# MOD-ADC-10.net
KiCad netlist of a schematic drawn in Altium Designer
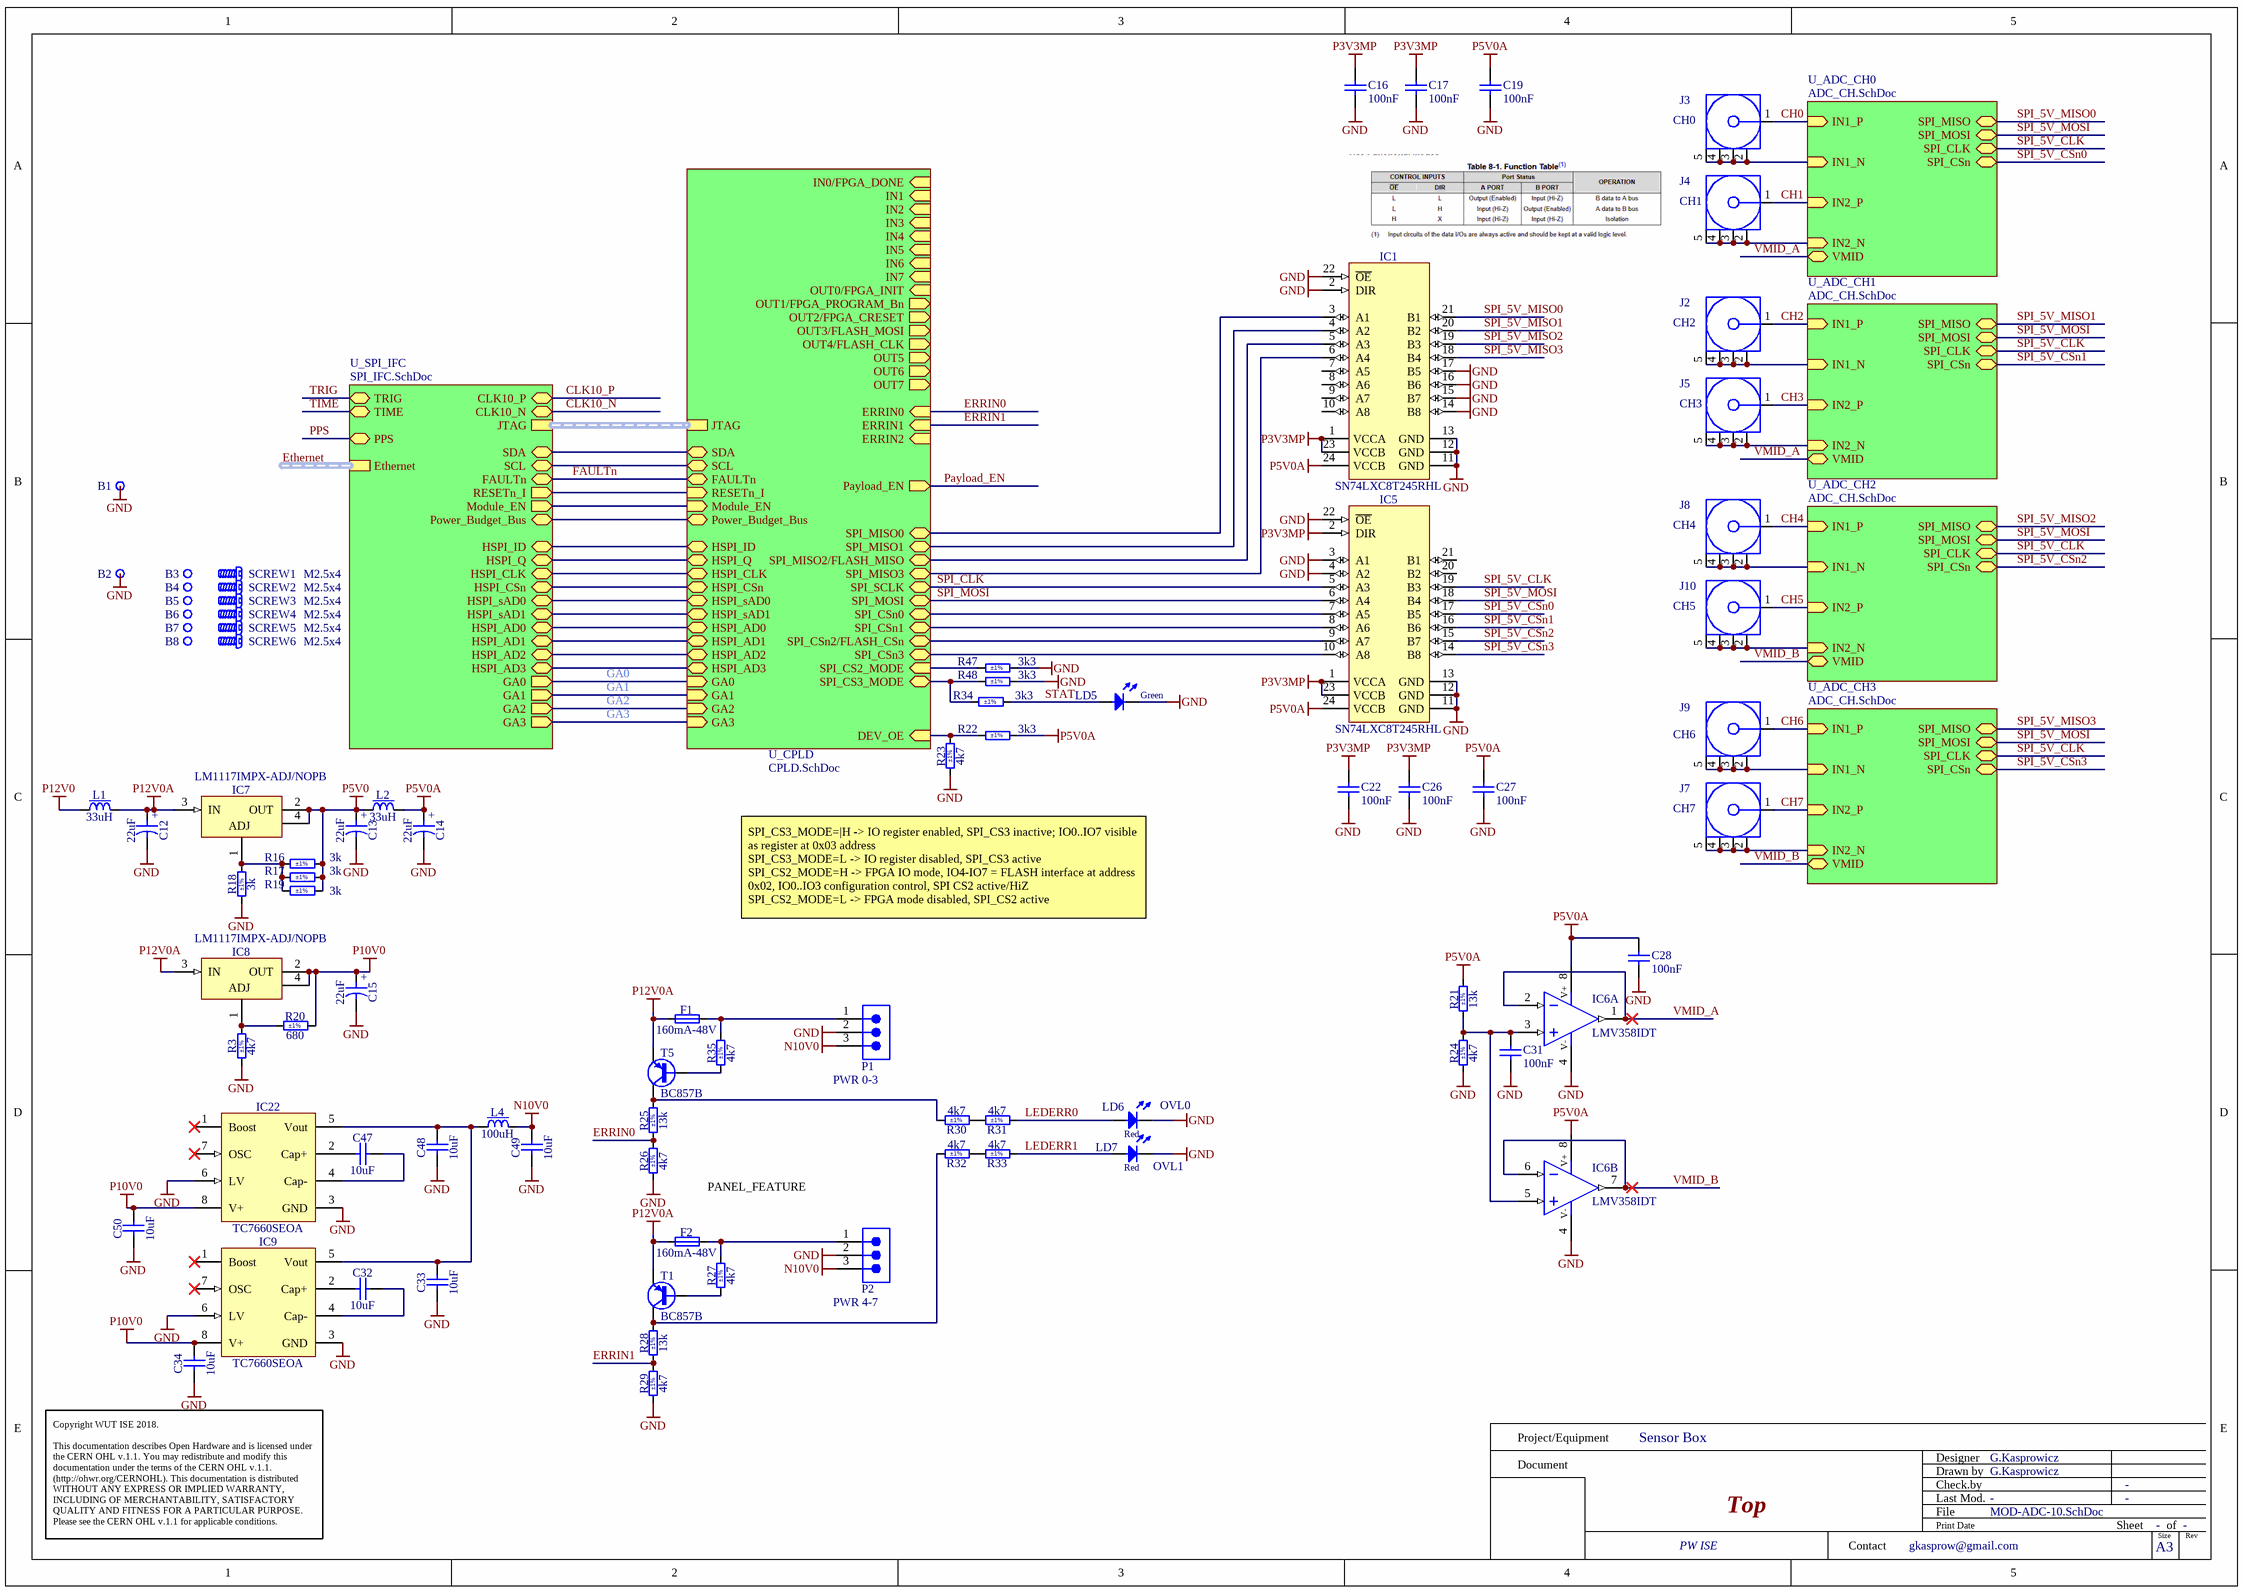
[diagram p0: MOD-ADC-10.SchDoc]

(export (version "E")
  (design (tool "Eeschema 10.0.6"))
  (components
    (comp (ref "B1")
      (value "Plated Hole")
      (footprint "MTG270_500")
      (description "Single Terminal Socket")
      (fields (field (name "PART NUMBER") "PLATED_HOLE2.7_PAD5.0") (field (name "AUTHOR") "CERN DEM JMW"))
      (libsource (lib "Eletro-mechanical") (part "Single Terminal Socket"))
    )
    (comp (ref "B2")
      (value "Plated Hole")
      (footprint "MTG270_500")
      (description "Single Terminal Socket")
      (fields (field (name "PART NUMBER") "PLATED_HOLE2.7_PAD5.0") (field (name "AUTHOR") "CERN DEM JMW"))
      (libsource (lib "Eletro-mechanical") (part "Single Terminal Socket"))
    )
    (comp (ref "B3")
      (value "Plated Hole")
      (footprint "MTG270_500")
      (description "Single Terminal Socket")
      (fields (field (name "PART NUMBER") "PLATED_HOLE2.7_PAD5.0") (field (name "AUTHOR") "CERN DEM JMW"))
      (libsource (lib "Eletro-mechanical") (part "Single Terminal Socket"))
    )
    (comp (ref "B4")
      (value "Plated Hole")
      (footprint "MTG270_500")
      (description "Single Terminal Socket")
      (fields (field (name "PART NUMBER") "PLATED_HOLE2.7_PAD5.0") (field (name "AUTHOR") "CERN DEM JMW"))
      (libsource (lib "Eletro-mechanical") (part "Single Terminal Socket"))
    )
    (comp (ref "B5")
      (value "Plated Hole")
      (footprint "MTG270_500")
      (description "Single Terminal Socket")
      (fields (field (name "PART NUMBER") "PLATED_HOLE2.7_PAD5.0") (field (name "AUTHOR") "CERN DEM JMW"))
      (libsource (lib "Eletro-mechanical") (part "Single Terminal Socket"))
    )
    (comp (ref "B6")
      (value "Plated Hole")
      (footprint "MTG270_500")
      (description "Single Terminal Socket")
      (fields (field (name "PART NUMBER") "PLATED_HOLE2.7_PAD5.0") (field (name "AUTHOR") "CERN DEM JMW"))
      (libsource (lib "Eletro-mechanical") (part "Single Terminal Socket"))
    )
    (comp (ref "B7")
      (value "Plated Hole")
      (footprint "MTG270_500")
      (description "Single Terminal Socket")
      (fields (field (name "PART NUMBER") "PLATED_HOLE2.7_PAD5.0") (field (name "AUTHOR") "CERN DEM JMW"))
      (libsource (lib "Eletro-mechanical") (part "Single Terminal Socket"))
    )
    (comp (ref "B8")
      (value "Plated Hole")
      (footprint "MTG270_500")
      (description "Single Terminal Socket")
      (fields (field (name "PART NUMBER") "PLATED_HOLE2.7_PAD5.0") (field (name "AUTHOR") "CERN DEM JMW"))
      (libsource (lib "Eletro-mechanical") (part "Single Terminal Socket"))
    )
    (comp (ref "C12")
      (value "22uF")
      (footprint "CAPMP3528X210N")
      (description "Polarised capacitor")
      (fields
        (field (name "PART NUMBER") "CTE3528-21_22UF_20V_10%")
        (field (name "VOLTAGE") "20V")
        (field (name "AUTHOR") "CERN DEM JLC")
      )
      (libsource (lib "Capacitors") (part "Capacitor - polarized"))
    )
    (comp (ref "C13")
      (value "22uF")
      (footprint "CAPMP3528X210N")
      (description "Polarised capacitor")
      (fields
        (field (name "PART NUMBER") "CTE3528-21_22UF_20V_10%")
        (field (name "VOLTAGE") "20V")
        (field (name "AUTHOR") "CERN DEM JLC")
      )
      (libsource (lib "Capacitors") (part "Capacitor - polarized"))
    )
    (comp (ref "C14")
      (value "22uF")
      (footprint "CAPMP3528X210N")
      (description "Polarised capacitor")
      (fields
        (field (name "PART NUMBER") "CTE3528-21_22UF_20V_10%")
        (field (name "VOLTAGE") "20V")
        (field (name "AUTHOR") "CERN DEM JLC")
      )
      (libsource (lib "Capacitors") (part "Capacitor - polarized"))
    )
    (comp (ref "C15")
      (value "22uF")
      (footprint "CAPMP3528X210N")
      (description "Polarised capacitor")
      (fields
        (field (name "PART NUMBER") "CTE3528-21_22UF_20V_10%")
        (field (name "VOLTAGE") "20V")
        (field (name "AUTHOR") "CERN DEM JLC")
      )
      (libsource (lib "Capacitors") (part "Capacitor - polarized"))
    )
    (comp (ref "C16")
      (value "100nF")
      (footprint "CAPC1005X55N")
      (description "Non-polarised capacitor")
      (fields
        (field (name "PART NUMBER") "CC0402_100NF_16V_10%_X7R")
        (field (name "VOLTAGE") "16V")
        (field (name "AUTHOR") "CERN DEM JLC")
      )
      (libsource (lib "Capacitors") (part "Capacitor - non polarized"))
    )
    (comp (ref "C17")
      (value "100nF")
      (footprint "CAPC1005X55N")
      (description "Non-polarised capacitor")
      (fields
        (field (name "PART NUMBER") "CC0402_100NF_16V_10%_X7R")
        (field (name "VOLTAGE") "16V")
        (field (name "AUTHOR") "CERN DEM JLC")
      )
      (libsource (lib "Capacitors") (part "Capacitor - non polarized"))
    )
    (comp (ref "C19")
      (value "100nF")
      (footprint "CAPC1005X55N")
      (description "Non-polarised capacitor")
      (fields
        (field (name "PART NUMBER") "CC0402_100NF_16V_10%_X7R")
        (field (name "VOLTAGE") "16V")
        (field (name "AUTHOR") "CERN DEM JLC")
      )
      (libsource (lib "Capacitors") (part "Capacitor - non polarized"))
    )
    (comp (ref "C22")
      (value "100nF")
      (footprint "CAPC1005X55N")
      (description "Non-polarised capacitor")
      (fields
        (field (name "PART NUMBER") "CC0402_100NF_16V_10%_X7R")
        (field (name "VOLTAGE") "16V")
        (field (name "AUTHOR") "CERN DEM JLC")
      )
      (libsource (lib "Capacitors") (part "Capacitor - non polarized"))
    )
    (comp (ref "C26")
      (value "100nF")
      (footprint "CAPC1005X55N")
      (description "Non-polarised capacitor")
      (fields
        (field (name "PART NUMBER") "CC0402_100NF_16V_10%_X7R")
        (field (name "VOLTAGE") "16V")
        (field (name "AUTHOR") "CERN DEM JLC")
      )
      (libsource (lib "Capacitors") (part "Capacitor - non polarized"))
    )
    (comp (ref "C27")
      (value "100nF")
      (footprint "CAPC1005X55N")
      (description "Non-polarised capacitor")
      (fields
        (field (name "PART NUMBER") "CC0402_100NF_16V_10%_X7R")
        (field (name "VOLTAGE") "16V")
        (field (name "AUTHOR") "CERN DEM JLC")
      )
      (libsource (lib "Capacitors") (part "Capacitor - non polarized"))
    )
    (comp (ref "C28")
      (value "100nF")
      (footprint "CAPC1005X55N")
      (description "Non-polarised capacitor")
      (fields
        (field (name "PART NUMBER") "CC0402_100NF_16V_10%_X7R")
        (field (name "VOLTAGE") "16V")
        (field (name "AUTHOR") "CERN DEM JLC")
      )
      (libsource (lib "Capacitors") (part "Capacitor - non polarized"))
    )
    (comp (ref "C31")
      (value "100nF")
      (footprint "CAPC1005X55N")
      (description "Non-polarised capacitor")
      (fields
        (field (name "PART NUMBER") "CC0402_100NF_16V_10%_X7R")
        (field (name "VOLTAGE") "16V")
        (field (name "AUTHOR") "CERN DEM JLC")
      )
      (libsource (lib "Capacitors") (part "Capacitor - non polarized"))
    )
    (comp (ref "C32")
      (value "10uF")
      (footprint "CAPC1608X80N")
      (description "Non-polarised capacitor")
      (fields
        (field (name "PART NUMBER") "CC0603_10UF_10V_10%_X5R")
        (field (name "VOLTAGE") "10V")
        (field (name "AUTHOR") "CERN DEM JLC")
      )
      (libsource (lib "Capacitors") (part "Capacitor - non polarized"))
    )
    (comp (ref "C33")
      (value "10uF")
      (footprint "CAPC1608X80N")
      (description "Non-polarised capacitor")
      (fields
        (field (name "PART NUMBER") "CC0603_10UF_10V_10%_X5R")
        (field (name "VOLTAGE") "10V")
        (field (name "AUTHOR") "CERN DEM JLC")
      )
      (libsource (lib "Capacitors") (part "Capacitor - non polarized"))
    )
    (comp (ref "C34")
      (value "10uF")
      (footprint "CAPC1608X80N")
      (description "Non-polarised capacitor")
      (fields
        (field (name "PART NUMBER") "CC0603_10UF_10V_10%_X5R")
        (field (name "VOLTAGE") "10V")
        (field (name "AUTHOR") "CERN DEM JLC")
      )
      (libsource (lib "Capacitors") (part "Capacitor - non polarized"))
    )
    (comp (ref "C47")
      (value "10uF")
      (footprint "CAPC1608X80N")
      (description "Non-polarised capacitor")
      (fields
        (field (name "PART NUMBER") "CC0603_10UF_10V_10%_X5R")
        (field (name "VOLTAGE") "10V")
        (field (name "AUTHOR") "CERN DEM JLC")
      )
      (libsource (lib "Capacitors") (part "Capacitor - non polarized"))
    )
    (comp (ref "C48")
      (value "10uF")
      (footprint "CAPC1608X80N")
      (description "Non-polarised capacitor")
      (fields
        (field (name "PART NUMBER") "CC0603_10UF_10V_10%_X5R")
        (field (name "VOLTAGE") "10V")
        (field (name "AUTHOR") "CERN DEM JLC")
      )
      (libsource (lib "Capacitors") (part "Capacitor - non polarized"))
    )
    (comp (ref "C49")
      (value "10uF")
      (footprint "CAPC1608X80N")
      (description "Non-polarised capacitor")
      (fields
        (field (name "PART NUMBER") "CC0603_10UF_10V_10%_X5R")
        (field (name "VOLTAGE") "10V")
        (field (name "AUTHOR") "CERN DEM JLC")
      )
      (libsource (lib "Capacitors") (part "Capacitor - non polarized"))
    )
    (comp (ref "C50")
      (value "10uF")
      (footprint "CAPC1608X80N")
      (description "Non-polarised capacitor")
      (fields
        (field (name "PART NUMBER") "CC0603_10UF_10V_10%_X5R")
        (field (name "VOLTAGE") "10V")
        (field (name "AUTHOR") "CERN DEM JLC")
      )
      (libsource (lib "Capacitors") (part "Capacitor - non polarized"))
    )
    (comp (ref "F1")
      (value "160mA-48V")
      (footprint "FUSRC3216X100N")
      (description "Fuse")
      (fields
        (field (name "PART NUMBER") "FUSR1206_TYCO_NANOSMD016F")
        (field (name "MANUFACTURER") "TYCO ELECTRONICS")
        (field (name "AUTHOR") "CERN DEM JLC")
      )
      (libsource (lib "Eletro-mechanical") (part "Fuse"))
    )
    (comp (ref "F2")
      (value "160mA-48V")
      (footprint "FUSRC3216X100N")
      (description "Fuse")
      (fields
        (field (name "PART NUMBER") "FUSR1206_TYCO_NANOSMD016F")
        (field (name "MANUFACTURER") "TYCO ELECTRONICS")
        (field (name "AUTHOR") "CERN DEM JLC")
      )
      (libsource (lib "Eletro-mechanical") (part "Fuse"))
    )
    (comp (ref "IC1")
      (value "SN74LXC8T245RHL")
      (footprint "TEXAS_RHL (S-PVQFN-N24)")
      (description "8-Bit Dual-Supply Bus Transceiver With Configurable Voltage Translation and 3-State Outputs")
      (fields (field (name "MANUFACTURER") "TEXAS INSTRUMENTS") (field (name "AUTHOR") "CERN DEM BC"))
      (libsource (lib "ICs And Semiconductors") (part "748T245"))
    )
    (comp (ref "IC5")
      (value "SN74LXC8T245RHL")
      (footprint "TEXAS_RHL (S-PVQFN-N24)")
      (description "8-Bit Dual-Supply Bus Transceiver With Configurable Voltage Translation and 3-State Outputs")
      (fields (field (name "MANUFACTURER") "TEXAS INSTRUMENTS") (field (name "AUTHOR") "CERN DEM BC"))
      (libsource (lib "ICs And Semiconductors") (part "748T245"))
    )
    (comp (ref "IC6")
      (value "LMV358IDT")
      (footprint "SOIC127P600X175-8N")
      (description "Dual Operational Amplifier")
      (fields (field (name "MANUFACTURER") "ST MICROELECTRONICS") (field (name "AUTHOR") "CERN DEM HF"))
      (libsource (lib "ICs And Semiconductors") (part "Operational Amplifier x2 Type1"))
    )
    (comp (ref "IC7")
      (value "LM1117IMPX-ADJ/NOPB")
      (footprint "SOT230P700X180-4N")
      (description "3-Terminal Regulator 1=Adj 2=OUT 3=IN 4=OUT")
      (fields
        (field (name "MANUFACTURER") "TEXAS INSTRUMENTS")
        (field (name "MANUFACTURER PART NUMBER") "LM1117IMPX-ADJ")
        (field (name "AUTHOR") "CERN DEM JLC")
      )
      (libsource (lib "ICs And Semiconductors") (part "REG3+1 1ADJ-2OUT-3IN+4OUT"))
    )
    (comp (ref "IC8")
      (value "LM1117IMPX-ADJ/NOPB")
      (footprint "SOT230P700X180-4N")
      (description "3-Terminal Regulator 1=Adj 2=OUT 3=IN 4=OUT")
      (fields
        (field (name "MANUFACTURER") "TEXAS INSTRUMENTS")
        (field (name "MANUFACTURER PART NUMBER") "LM1117IMPX-ADJ")
        (field (name "AUTHOR") "CERN DEM JLC")
      )
      (libsource (lib "ICs And Semiconductors") (part "REG3+1 1ADJ-2OUT-3IN+4OUT"))
    )
    (comp (ref "IC9")
      (value "TC7660SEOA")
      (footprint "SOIC127P600X175-8N")
      (description "Super Charge Pump DC-to-DC Voltage Converter")
      (fields (field (name "MANUFACTURER") "MICROCHIP TECHNOLOGY") (field (name "AUTHOR") "CERN DEM HF"))
      (libsource (lib "ICs And Semiconductors") (part "TC7660S"))
    )
    (comp (ref "IC22")
      (value "TC7660SEOA")
      (footprint "SOIC127P600X175-8N")
      (description "Super Charge Pump DC-to-DC Voltage Converter")
      (fields (field (name "MANUFACTURER") "MICROCHIP TECHNOLOGY") (field (name "AUTHOR") "CERN DEM HF"))
      (libsource (lib "ICs And Semiconductors") (part "TC7660S"))
    )
    (comp (ref "J2")
      (value "60611002111502")
      (footprint "60611002111502")
      (description "WR-MCX PCB Jack, THT, Right Angle, Solder Leg 1.73mm")
      (fields (field (name "MANUFACTURER") "Wurth Elektronik") (field (name "PANEL_LABEL") "CH2"))
      (libsource (lib "Altium_WR-MCX (rev22a)") (part "60611002111502"))
    )
    (comp (ref "J3")
      (value "60611002111502")
      (footprint "60611002111502")
      (description "WR-MCX PCB Jack, THT, Right Angle, Solder Leg 1.73mm")
      (fields (field (name "MANUFACTURER") "Wurth Elektronik") (field (name "PANEL_LABEL") "CH0"))
      (libsource (lib "Altium_WR-MCX (rev22a)") (part "60611002111502"))
    )
    (comp (ref "J4")
      (value "60611002111502")
      (footprint "60611002111502")
      (description "WR-MCX PCB Jack, THT, Right Angle, Solder Leg 1.73mm")
      (fields (field (name "MANUFACTURER") "Wurth Elektronik") (field (name "PANEL_LABEL") "CH1"))
      (libsource (lib "Altium_WR-MCX (rev22a)") (part "60611002111502"))
    )
    (comp (ref "J5")
      (value "60611002111502")
      (footprint "60611002111502")
      (description "WR-MCX PCB Jack, THT, Right Angle, Solder Leg 1.73mm")
      (fields (field (name "MANUFACTURER") "Wurth Elektronik") (field (name "PANEL_LABEL") "CH3"))
      (libsource (lib "Altium_WR-MCX (rev22a)") (part "60611002111502"))
    )
    (comp (ref "J7")
      (value "60611002111502")
      (footprint "60611002111502")
      (description "WR-MCX PCB Jack, THT, Right Angle, Solder Leg 1.73mm")
      (fields (field (name "MANUFACTURER") "Wurth Elektronik") (field (name "PANEL_LABEL") "CH7"))
      (libsource (lib "Altium_WR-MCX (rev22a)") (part "60611002111502"))
    )
    (comp (ref "J8")
      (value "60611002111502")
      (footprint "60611002111502")
      (description "WR-MCX PCB Jack, THT, Right Angle, Solder Leg 1.73mm")
      (fields (field (name "MANUFACTURER") "Wurth Elektronik") (field (name "PANEL_LABEL") "CH4"))
      (libsource (lib "Altium_WR-MCX (rev22a)") (part "60611002111502"))
    )
    (comp (ref "J9")
      (value "60611002111502")
      (footprint "60611002111502")
      (description "WR-MCX PCB Jack, THT, Right Angle, Solder Leg 1.73mm")
      (fields (field (name "MANUFACTURER") "Wurth Elektronik") (field (name "PANEL_LABEL") "CH6"))
      (libsource (lib "Altium_WR-MCX (rev22a)") (part "60611002111502"))
    )
    (comp (ref "J10")
      (value "60611002111502")
      (footprint "60611002111502")
      (description "WR-MCX PCB Jack, THT, Right Angle, Solder Leg 1.73mm")
      (fields (field (name "MANUFACTURER") "Wurth Elektronik") (field (name "PANEL_LABEL") "CH5"))
      (libsource (lib "Altium_WR-MCX (rev22a)") (part "60611002111502"))
    )
    (comp (ref "L1")
      (value "33uH")
      (footprint "IND_WURTH_WE-TPC_4828")
      (description "Inductor With Core")
      (fields
        (field (name "PART NUMBER") "IND_33UH_30%_WURTH_WE-TPC_744043330")
        (field (name "POWER") "820mA")
        (field (name "AUTHOR") "CERN DEM JLC")
      )
      (libsource (lib "Inductors & Transformers") (part "Inductor With Magnetic core"))
    )
    (comp (ref "L2")
      (value "33uH")
      (footprint "IND_WURTH_WE-TPC_4828")
      (description "Inductor With Core")
      (fields
        (field (name "PART NUMBER") "IND_33UH_30%_WURTH_WE-TPC_744043330")
        (field (name "POWER") "820mA")
        (field (name "AUTHOR") "CERN DEM JLC")
      )
      (libsource (lib "Inductors & Transformers") (part "Inductor With Magnetic core"))
    )
    (comp (ref "L4")
      (value "100uH")
      (footprint "INDM3225X240N")
      (description "Inductor With Core")
      (fields
        (field (name "PART NUMBER") "IND1210_100UH_10%_EPCOS_B82422H")
        (field (name "POWER") "150mA")
        (field (name "AUTHOR") "CERN DEM JLC")
      )
      (libsource (lib "Inductors & Transformers") (part "Inductor With Magnetic core"))
    )
    (comp (ref "LD5")
      (value "Green")
      (footprint "LED_AVAGO_HSME-C120")
      (description "LED Green 1C 2A")
      (fields
        (field (name "PART NUMBER") "LED_AVAGO_HSME-C120")
        (field (name "MANUFACTURER") "AVAGO TECHNOLOGIES")
        (field (name "AUTHOR") "CERN DEM JMW")
      )
      (libsource (lib "ICs And Semiconductors") (part "LED Green 1C 2A"))
    )
    (comp (ref "LD6")
      (value "Red")
      (footprint "LED_AVAGO_HSMC-C120")
      (description "LED Red 1C 2A")
      (fields
        (field (name "PART NUMBER") "LED_AVAGO_HSMC-C120")
        (field (name "MANUFACTURER") "AVAGO TECHNOLOGIES")
        (field (name "PANEL_LABEL") "OVL0")
        (field (name "AUTHOR") "CERN DEM JMW")
      )
      (libsource (lib "ICs And Semiconductors") (part "LED Red 1C 2A"))
    )
    (comp (ref "LD7")
      (value "Red")
      (footprint "LED_AVAGO_HSMC-C120")
      (description "LED Red 1C 2A")
      (fields
        (field (name "PART NUMBER") "LED_AVAGO_HSMC-C120")
        (field (name "MANUFACTURER") "AVAGO TECHNOLOGIES")
        (field (name "PANEL_LABEL") "OVL1")
        (field (name "AUTHOR") "CERN DEM JMW")
      )
      (libsource (lib "ICs And Semiconductors") (part "LED Red 1C 2A"))
    )
    (comp (ref "P1")
      (value "691382010003")
      (footprint "691382010003")
      (description "WR-TBL Series 382 Horizontal PCB Header, THT, pitch 2.5mm, 3p")
      (fields (field (name "MANUFACTURER") "Wurth Elektronik") (field (name "PANEL_LABEL") "PWR 0-3"))
      (libsource (lib "Altium_WR-TBL (rev23f)") (part "691382010003"))
    )
    (comp (ref "P2")
      (value "691382010003")
      (footprint "691382010003")
      (description "WR-TBL Series 382 Horizontal PCB Header, THT, pitch 2.5mm, 3p")
      (fields (field (name "MANUFACTURER") "Wurth Elektronik") (field (name "PANEL_LABEL") "PWR 4-7"))
      (libsource (lib "Altium_WR-TBL (rev23f)") (part "691382010003"))
    )
    (comp (ref "R3")
      (value "4k7")
      (footprint "RESC1608X55N")
      (description "Resistor - 1%")
      (fields
        (field (name "TOLERANCE") "±1%")
        (field (name "PART NUMBER") "R0603_4K7_1%_0.1W_100PPM")
        (field (name "POWER") "0.1W")
        (field (name "AUTHOR") "CERN DEM JLC")
      )
      (libsource (lib "Resistors") (part "Resistor - 1%"))
    )
    (comp (ref "R16")
      (value "3k")
      (footprint "RESC1608X55N")
      (description "Resistor - 1%")
      (fields
        (field (name "TOLERANCE") "±1%")
        (field (name "PART NUMBER") "R0603_3K_1%_0.33W_100PPM_VISHAY_CRCW-HP e3")
        (field (name "POWER") "0.33W")
        (field (name "AUTHOR") "CERN DEM BC")
      )
      (libsource (lib "Resistors") (part "Resistor - 1%"))
    )
    (comp (ref "R17")
      (value "3k")
      (footprint "RESC1608X55N")
      (description "Resistor - 1%")
      (fields
        (field (name "TOLERANCE") "±1%")
        (field (name "PART NUMBER") "R0603_3K_1%_0.33W_100PPM_VISHAY_CRCW-HP e3")
        (field (name "POWER") "0.33W")
        (field (name "AUTHOR") "CERN DEM BC")
      )
      (libsource (lib "Resistors") (part "Resistor - 1%"))
    )
    (comp (ref "R18")
      (value "3k")
      (footprint "RESC1608X55N")
      (description "Resistor - 1%")
      (fields
        (field (name "TOLERANCE") "±1%")
        (field (name "PART NUMBER") "R0603_3K_1%_0.33W_100PPM_VISHAY_CRCW-HP e3")
        (field (name "POWER") "0.33W")
        (field (name "AUTHOR") "CERN DEM BC")
      )
      (libsource (lib "Resistors") (part "Resistor - 1%"))
    )
    (comp (ref "R19")
      (value "3k")
      (footprint "RESC1608X55N")
      (description "Resistor - 1%")
      (fields
        (field (name "TOLERANCE") "±1%")
        (field (name "PART NUMBER") "R0603_3K_1%_0.33W_100PPM_VISHAY_CRCW-HP e3")
        (field (name "POWER") "0.33W")
        (field (name "AUTHOR") "CERN DEM BC")
      )
      (libsource (lib "Resistors") (part "Resistor - 1%"))
    )
    (comp (ref "R20")
      (value "680")
      (footprint "RESC1608X55N")
      (description "Resistor - 1%")
      (fields
        (field (name "TOLERANCE") "±1%")
        (field (name "PART NUMBER") "R0603_680R_1%_0.1W_100PPM")
        (field (name "POWER") "0.1W")
        (field (name "AUTHOR") "CERN DEM JLC")
      )
      (libsource (lib "Resistors") (part "Resistor - 1%"))
    )
    (comp (ref "R21")
      (value "13k")
      (footprint "RESC1005X40N")
      (description "Resistor - 1%")
      (fields
        (field (name "TOLERANCE") "±1%")
        (field (name "PART NUMBER") "R0402_13K_1%_0.0625W_100PPM")
        (field (name "POWER") "0.0625W")
        (field (name "AUTHOR") "CERN DEM JLC")
      )
      (libsource (lib "Resistors") (part "Resistor - 1%"))
    )
    (comp (ref "R22")
      (value "3k3")
      (footprint "RESC1005X40N")
      (description "Resistor - 1%")
      (fields
        (field (name "TOLERANCE") "±1%")
        (field (name "PART NUMBER") "R0402_3K3_1%_0.0625W_100PPM")
        (field (name "POWER") "0.0625W")
        (field (name "AUTHOR") "CERN DEM JLC")
      )
      (libsource (lib "Resistors") (part "Resistor - 1%"))
    )
    (comp (ref "R23")
      (value "4k7")
      (footprint "RESC1608X55N")
      (description "Resistor - 1%")
      (fields
        (field (name "TOLERANCE") "±1%")
        (field (name "PART NUMBER") "R0603_4K7_1%_0.1W_100PPM")
        (field (name "POWER") "0.1W")
        (field (name "AUTHOR") "CERN DEM JLC")
      )
      (libsource (lib "Resistors") (part "Resistor - 1%"))
    )
    (comp (ref "R24")
      (value "4k7")
      (footprint "RESC1608X55N")
      (description "Resistor - 1%")
      (fields
        (field (name "TOLERANCE") "±1%")
        (field (name "PART NUMBER") "R0603_4K7_1%_0.1W_100PPM")
        (field (name "POWER") "0.1W")
        (field (name "AUTHOR") "CERN DEM JLC")
      )
      (libsource (lib "Resistors") (part "Resistor - 1%"))
    )
    (comp (ref "R25")
      (value "13k")
      (footprint "RESC1005X40N")
      (description "Resistor - 1%")
      (fields
        (field (name "TOLERANCE") "±1%")
        (field (name "PART NUMBER") "R0402_13K_1%_0.0625W_100PPM")
        (field (name "POWER") "0.0625W")
        (field (name "AUTHOR") "CERN DEM JLC")
      )
      (libsource (lib "Resistors") (part "Resistor - 1%"))
    )
    (comp (ref "R26")
      (value "4k7")
      (footprint "RESC1608X55N")
      (description "Resistor - 1%")
      (fields
        (field (name "TOLERANCE") "±1%")
        (field (name "PART NUMBER") "R0603_4K7_1%_0.1W_100PPM")
        (field (name "POWER") "0.1W")
        (field (name "AUTHOR") "CERN DEM JLC")
      )
      (libsource (lib "Resistors") (part "Resistor - 1%"))
    )
    (comp (ref "R27")
      (value "4k7")
      (footprint "RESC1608X55N")
      (description "Resistor - 1%")
      (fields
        (field (name "TOLERANCE") "±1%")
        (field (name "PART NUMBER") "R0603_4K7_1%_0.1W_100PPM")
        (field (name "POWER") "0.1W")
        (field (name "AUTHOR") "CERN DEM JLC")
      )
      (libsource (lib "Resistors") (part "Resistor - 1%"))
    )
    (comp (ref "R28")
      (value "13k")
      (footprint "RESC1005X40N")
      (description "Resistor - 1%")
      (fields
        (field (name "TOLERANCE") "±1%")
        (field (name "PART NUMBER") "R0402_13K_1%_0.0625W_100PPM")
        (field (name "POWER") "0.0625W")
        (field (name "AUTHOR") "CERN DEM JLC")
      )
      (libsource (lib "Resistors") (part "Resistor - 1%"))
    )
    (comp (ref "R29")
      (value "4k7")
      (footprint "RESC1608X55N")
      (description "Resistor - 1%")
      (fields
        (field (name "TOLERANCE") "±1%")
        (field (name "PART NUMBER") "R0603_4K7_1%_0.1W_100PPM")
        (field (name "POWER") "0.1W")
        (field (name "AUTHOR") "CERN DEM JLC")
      )
      (libsource (lib "Resistors") (part "Resistor - 1%"))
    )
    (comp (ref "R30")
      (value "4k7")
      (footprint "RESC1608X55N")
      (description "Resistor - 1%")
      (fields
        (field (name "TOLERANCE") "±1%")
        (field (name "PART NUMBER") "R0603_4K7_1%_0.1W_100PPM")
        (field (name "POWER") "0.1W")
        (field (name "AUTHOR") "CERN DEM JLC")
      )
      (libsource (lib "Resistors") (part "Resistor - 1%"))
    )
    (comp (ref "R31")
      (value "4k7")
      (footprint "RESC1608X55N")
      (description "Resistor - 1%")
      (fields
        (field (name "TOLERANCE") "±1%")
        (field (name "PART NUMBER") "R0603_4K7_1%_0.1W_100PPM")
        (field (name "POWER") "0.1W")
        (field (name "AUTHOR") "CERN DEM JLC")
      )
      (libsource (lib "Resistors") (part "Resistor - 1%"))
    )
    (comp (ref "R32")
      (value "4k7")
      (footprint "RESC1608X55N")
      (description "Resistor - 1%")
      (fields
        (field (name "TOLERANCE") "±1%")
        (field (name "PART NUMBER") "R0603_4K7_1%_0.1W_100PPM")
        (field (name "POWER") "0.1W")
        (field (name "AUTHOR") "CERN DEM JLC")
      )
      (libsource (lib "Resistors") (part "Resistor - 1%"))
    )
    (comp (ref "R33")
      (value "4k7")
      (footprint "RESC1608X55N")
      (description "Resistor - 1%")
      (fields
        (field (name "TOLERANCE") "±1%")
        (field (name "PART NUMBER") "R0603_4K7_1%_0.1W_100PPM")
        (field (name "POWER") "0.1W")
        (field (name "AUTHOR") "CERN DEM JLC")
      )
      (libsource (lib "Resistors") (part "Resistor - 1%"))
    )
    (comp (ref "R34")
      (value "3k3")
      (footprint "RESC1005X40N")
      (description "Resistor - 1%")
      (fields
        (field (name "TOLERANCE") "±1%")
        (field (name "PART NUMBER") "R0402_3K3_1%_0.0625W_100PPM")
        (field (name "POWER") "0.0625W")
        (field (name "AUTHOR") "CERN DEM JLC")
      )
      (libsource (lib "Resistors") (part "Resistor - 1%"))
    )
    (comp (ref "R35")
      (value "4k7")
      (footprint "RESC1608X55N")
      (description "Resistor - 1%")
      (fields
        (field (name "TOLERANCE") "±1%")
        (field (name "PART NUMBER") "R0603_4K7_1%_0.1W_100PPM")
        (field (name "POWER") "0.1W")
        (field (name "AUTHOR") "CERN DEM JLC")
      )
      (libsource (lib "Resistors") (part "Resistor - 1%"))
    )
    (comp (ref "R47")
      (value "3k3")
      (footprint "RESC1005X40N")
      (description "Resistor - 1%")
      (fields
        (field (name "TOLERANCE") "±1%")
        (field (name "PART NUMBER") "R0402_3K3_1%_0.0625W_100PPM")
        (field (name "POWER") "0.0625W")
        (field (name "AUTHOR") "CERN DEM JLC")
      )
      (libsource (lib "Resistors") (part "Resistor - 1%"))
    )
    (comp (ref "R48")
      (value "3k3")
      (footprint "RESC1005X40N")
      (description "Resistor - 1%")
      (fields
        (field (name "TOLERANCE") "±1%")
        (field (name "PART NUMBER") "R0402_3K3_1%_0.0625W_100PPM")
        (field (name "POWER") "0.0625W")
        (field (name "AUTHOR") "CERN DEM JLC")
      )
      (libsource (lib "Resistors") (part "Resistor - 1%"))
    )
    (comp (ref "SCREW1")
      (value "M2.5x4")
      (footprint "BOSSARD_BN5687-3061587_v")
      (description "Screw")
      (fields
        (field (name "PART NUMBER") "BOSSARD_BN5687-3061587_v")
        (field (name "MANUFACTURER") "BOSSARD")
        (field (name "AUTHOR") "CERN DEM JLC")
      )
      (libsource (lib "Eletro-mechanical") (part "Screw"))
    )
    (comp (ref "SCREW2")
      (value "M2.5x4")
      (footprint "BOSSARD_BN5687-3061587_v")
      (description "Screw")
      (fields
        (field (name "PART NUMBER") "BOSSARD_BN5687-3061587_v")
        (field (name "MANUFACTURER") "BOSSARD")
        (field (name "AUTHOR") "CERN DEM JLC")
      )
      (libsource (lib "Eletro-mechanical") (part "Screw"))
    )
    (comp (ref "SCREW3")
      (value "M2.5x4")
      (footprint "BOSSARD_BN5687-3061587_v")
      (description "Screw")
      (fields
        (field (name "PART NUMBER") "BOSSARD_BN5687-3061587_v")
        (field (name "MANUFACTURER") "BOSSARD")
        (field (name "AUTHOR") "CERN DEM JLC")
      )
      (libsource (lib "Eletro-mechanical") (part "Screw"))
    )
    (comp (ref "SCREW4")
      (value "M2.5x4")
      (footprint "BOSSARD_BN5687-3061587_v")
      (description "Screw")
      (fields
        (field (name "PART NUMBER") "BOSSARD_BN5687-3061587_v")
        (field (name "MANUFACTURER") "BOSSARD")
        (field (name "AUTHOR") "CERN DEM JLC")
      )
      (libsource (lib "Eletro-mechanical") (part "Screw"))
    )
    (comp (ref "SCREW5")
      (value "M2.5x4")
      (footprint "BOSSARD_BN5687-3061587_v")
      (description "Screw")
      (fields
        (field (name "PART NUMBER") "BOSSARD_BN5687-3061587_v")
        (field (name "MANUFACTURER") "BOSSARD")
        (field (name "AUTHOR") "CERN DEM JLC")
      )
      (libsource (lib "Eletro-mechanical") (part "Screw"))
    )
    (comp (ref "SCREW6")
      (value "M2.5x4")
      (footprint "BOSSARD_BN5687-3061587_v")
      (description "Screw")
      (fields
        (field (name "PART NUMBER") "BOSSARD_BN5687-3061587_v")
        (field (name "MANUFACTURER") "BOSSARD")
        (field (name "AUTHOR") "CERN DEM JLC")
      )
      (libsource (lib "Eletro-mechanical") (part "Screw"))
    )
    (comp (ref "T1")
      (value "BC857B")
      (footprint "SOT95P230X110-3N")
      (description "PNP Transistor")
      (fields (field (name "MANUFACTURER") "NXP SEMICONDUCTORS") (field (name "AUTHOR") "CERN DEM JLC"))
      (libsource (lib "ICs And Semiconductors") (part "PNP B1 E2 C3"))
    )
    (comp (ref "T5")
      (value "BC857B")
      (footprint "SOT95P230X110-3N")
      (description "PNP Transistor")
      (fields (field (name "MANUFACTURER") "NXP SEMICONDUCTORS") (field (name "AUTHOR") "CERN DEM JLC"))
      (libsource (lib "ICs And Semiconductors") (part "PNP B1 E2 C3"))
    )
  )
  (nets
    (net (code "2") (name "/CH0") (class "Default")
      (node (ref "J3") (pin "1") (pinfunction "Signal_1") (pintype "passive"))
    )
    (net (code "3") (name "/CH1") (class "Default")
      (node (ref "J4") (pin "1") (pinfunction "Signal_1") (pintype "passive"))
    )
    (net (code "4") (name "/CH2") (class "Default")
      (node (ref "J2") (pin "1") (pinfunction "Signal_1") (pintype "passive"))
    )
    (net (code "5") (name "/CH3") (class "Default")
      (node (ref "J5") (pin "1") (pinfunction "Signal_1") (pintype "passive"))
    )
    (net (code "6") (name "/CH4") (class "Default")
      (node (ref "J8") (pin "1") (pinfunction "Signal_1") (pintype "passive"))
    )
    (net (code "7") (name "/CH5") (class "Default")
      (node (ref "J10") (pin "1") (pinfunction "Signal_1") (pintype "passive"))
    )
    (net (code "8") (name "/CH6") (class "Default")
      (node (ref "J9") (pin "1") (pinfunction "Signal_1") (pintype "passive"))
    )
    (net (code "9") (name "/CH7") (class "Default")
      (node (ref "J7") (pin "1") (pinfunction "Signal_1") (pintype "passive"))
    )
    (net (code "12") (name "/DEV_OE") (class "Default")
      (node (ref "R22") (pin "1") (pinfunction "1_1") (pintype "passive"))
      (node (ref "R23") (pin "2") (pinfunction "2_2") (pintype "passive"))
    )
    (net (code "13") (name "/ERRIN0") (class "Default")
      (node (ref "R25") (pin "1") (pinfunction "1_1") (pintype "passive"))
      (node (ref "R26") (pin "2") (pinfunction "2_2") (pintype "passive"))
    )
    (net (code "14") (name "/ERRIN1") (class "Default")
      (node (ref "R28") (pin "1") (pinfunction "1_1") (pintype "passive"))
      (node (ref "R29") (pin "2") (pinfunction "2_2") (pintype "passive"))
    )
    (net (code "33") (name "/IN1_N") (class "Default")
      (node (ref "J2") (pin "2") (pinfunction "GND_2") (pintype "passive"))
      (node (ref "J2") (pin "3") (pinfunction "GND_3") (pintype "passive"))
      (node (ref "J2") (pin "4") (pinfunction "GND_4") (pintype "passive"))
      (node (ref "J2") (pin "5") (pinfunction "GND_5") (pintype "passive"))
    )
    (net (code "34") (name "/IN1_N_1") (class "Default")
      (node (ref "J9") (pin "2") (pinfunction "GND_2") (pintype "passive"))
      (node (ref "J9") (pin "3") (pinfunction "GND_3") (pintype "passive"))
      (node (ref "J9") (pin "4") (pinfunction "GND_4") (pintype "passive"))
      (node (ref "J9") (pin "5") (pinfunction "GND_5") (pintype "passive"))
    )
    (net (code "35") (name "/IN1_N_2") (class "Default")
      (node (ref "J8") (pin "2") (pinfunction "GND_2") (pintype "passive"))
      (node (ref "J8") (pin "3") (pinfunction "GND_3") (pintype "passive"))
      (node (ref "J8") (pin "4") (pinfunction "GND_4") (pintype "passive"))
      (node (ref "J8") (pin "5") (pinfunction "GND_5") (pintype "passive"))
    )
    (net (code "36") (name "/IN1_N_3") (class "Default")
      (node (ref "J3") (pin "2") (pinfunction "GND_2") (pintype "passive"))
      (node (ref "J3") (pin "3") (pinfunction "GND_3") (pintype "passive"))
      (node (ref "J3") (pin "4") (pinfunction "GND_4") (pintype "passive"))
      (node (ref "J3") (pin "5") (pinfunction "GND_5") (pintype "passive"))
    )
    (net (code "38") (name "/IN2_N") (class "Default")
      (node (ref "J5") (pin "2") (pinfunction "GND_2") (pintype "passive"))
      (node (ref "J5") (pin "3") (pinfunction "GND_3") (pintype "passive"))
      (node (ref "J5") (pin "4") (pinfunction "GND_4") (pintype "passive"))
      (node (ref "J5") (pin "5") (pinfunction "GND_5") (pintype "passive"))
    )
    (net (code "39") (name "/IN2_N_1") (class "Default")
      (node (ref "J7") (pin "2") (pinfunction "GND_2") (pintype "passive"))
      (node (ref "J7") (pin "3") (pinfunction "GND_3") (pintype "passive"))
      (node (ref "J7") (pin "4") (pinfunction "GND_4") (pintype "passive"))
      (node (ref "J7") (pin "5") (pinfunction "GND_5") (pintype "passive"))
    )
    (net (code "40") (name "/IN2_N_2") (class "Default")
      (node (ref "J10") (pin "2") (pinfunction "GND_2") (pintype "passive"))
      (node (ref "J10") (pin "3") (pinfunction "GND_3") (pintype "passive"))
      (node (ref "J10") (pin "4") (pinfunction "GND_4") (pintype "passive"))
      (node (ref "J10") (pin "5") (pinfunction "GND_5") (pintype "passive"))
    )
    (net (code "41") (name "/IN2_N_3") (class "Default")
      (node (ref "J4") (pin "2") (pinfunction "GND_2") (pintype "passive"))
      (node (ref "J4") (pin "3") (pinfunction "GND_3") (pintype "passive"))
      (node (ref "J4") (pin "4") (pinfunction "GND_4") (pintype "passive"))
      (node (ref "J4") (pin "5") (pinfunction "GND_5") (pintype "passive"))
    )
    (net (code "48") (name "/LEDERR0") (class "Default")
      (node (ref "LD6") (pin "2") (pinfunction "A_2") (pintype "passive"))
      (node (ref "R31") (pin "1") (pinfunction "1_1") (pintype "passive"))
    )
    (net (code "49") (name "/LEDERR1") (class "Default")
      (node (ref "LD7") (pin "2") (pinfunction "A_2") (pintype "passive"))
      (node (ref "R33") (pin "1") (pinfunction "1_1") (pintype "passive"))
    )
    (net (code "65") (name "/SPI_5V_CLK") (class "Default")
      (node (ref "IC5") (pin "19") (pinfunction "B3_19") (pintype "bidirectional"))
    )
    (net (code "66") (name "/SPI_5V_CSn0") (class "Default")
      (node (ref "IC5") (pin "17") (pinfunction "B5_17") (pintype "bidirectional"))
    )
    (net (code "67") (name "/SPI_5V_CSn1") (class "Default")
      (node (ref "IC5") (pin "16") (pinfunction "B6_16") (pintype "bidirectional"))
    )
    (net (code "68") (name "/SPI_5V_CSn2") (class "Default")
      (node (ref "IC5") (pin "15") (pinfunction "B7_15") (pintype "bidirectional"))
    )
    (net (code "69") (name "/SPI_5V_CSn3") (class "Default")
      (node (ref "IC5") (pin "14") (pinfunction "B8_14") (pintype "bidirectional"))
    )
    (net (code "70") (name "/SPI_5V_MISO0") (class "Default")
      (node (ref "IC1") (pin "21") (pinfunction "B1_21") (pintype "bidirectional"))
    )
    (net (code "71") (name "/SPI_5V_MISO1") (class "Default")
      (node (ref "IC1") (pin "20") (pinfunction "B2_20") (pintype "bidirectional"))
    )
    (net (code "72") (name "/SPI_5V_MISO2") (class "Default")
      (node (ref "IC1") (pin "19") (pinfunction "B3_19") (pintype "bidirectional"))
    )
    (net (code "73") (name "/SPI_5V_MISO3") (class "Default")
      (node (ref "IC1") (pin "18") (pinfunction "B4_18") (pintype "bidirectional"))
    )
    (net (code "74") (name "/SPI_5V_MOSI") (class "Default")
      (node (ref "IC5") (pin "18") (pinfunction "B4_18") (pintype "bidirectional"))
    )
    (net (code "75") (name "/SPI_CLK") (class "Default")
      (node (ref "IC5") (pin "5") (pinfunction "A3_5") (pintype "bidirectional"))
    )
    (net (code "76") (name "/SPI_CS2_MODE") (class "Default")
      (node (ref "R47") (pin "1") (pinfunction "1_1") (pintype "passive"))
    )
    (net (code "77") (name "/SPI_CS3_MODE") (class "Default")
      (node (ref "R34") (pin "2") (pinfunction "2_2") (pintype "passive"))
      (node (ref "R48") (pin "1") (pinfunction "1_1") (pintype "passive"))
    )
    (net (code "78") (name "/SPI_CSn0") (class "Default")
      (node (ref "IC5") (pin "7") (pinfunction "A5_7") (pintype "bidirectional"))
    )
    (net (code "79") (name "/SPI_CSn1") (class "Default")
      (node (ref "IC5") (pin "8") (pinfunction "A6_8") (pintype "bidirectional"))
    )
    (net (code "80") (name "/SPI_CSn2{slash}FLASH_CSn") (class "Default")
      (node (ref "IC5") (pin "9") (pinfunction "A7_9") (pintype "bidirectional"))
    )
    (net (code "81") (name "/SPI_CSn3") (class "Default")
      (node (ref "IC5") (pin "10") (pinfunction "A8_10") (pintype "bidirectional"))
    )
    (net (code "82") (name "/SPI_MISO0") (class "Default")
      (node (ref "IC1") (pin "3") (pinfunction "A1_3") (pintype "bidirectional"))
    )
    (net (code "83") (name "/SPI_MISO1") (class "Default")
      (node (ref "IC1") (pin "4") (pinfunction "A2_4") (pintype "bidirectional"))
    )
    (net (code "84") (name "/SPI_MISO2{slash}FLASH_MISO") (class "Default")
      (node (ref "IC1") (pin "5") (pinfunction "A3_5") (pintype "bidirectional"))
    )
    (net (code "85") (name "/SPI_MISO3") (class "Default")
      (node (ref "IC1") (pin "6") (pinfunction "A4_6") (pintype "bidirectional"))
    )
    (net (code "86") (name "/SPI_MOSI") (class "Default")
      (node (ref "IC5") (pin "6") (pinfunction "A4_6") (pintype "bidirectional"))
    )
    (net (code "87") (name "/STAT") (class "Default")
      (node (ref "LD5") (pin "2") (pinfunction "A_2") (pintype "passive"))
      (node (ref "R34") (pin "1") (pinfunction "1_1") (pintype "passive"))
    )
    (net (code "90") (name "/VMID_A") (class "Default")
      (node (ref "IC6") (pin "1") (pinfunction "OUT_1") (pintype "output"))
      (node (ref "IC6") (pin "2") (pinfunction "IN-_2") (pintype "input"))
    )
    (net (code "91") (name "/VMID_B") (class "Default")
      (node (ref "IC6") (pin "6") (pinfunction "IN-_6") (pintype "input"))
      (node (ref "IC6") (pin "7") (pinfunction "OUT_7") (pintype "output"))
    )
    (net (code "93") (name "GND") (class "Default")
      (node (ref "B1") (pin "1") (pinfunction "1_1") (pintype "bidirectional"))
      (node (ref "B2") (pin "1") (pinfunction "1_1") (pintype "bidirectional"))
      (node (ref "C12") (pin "2") (pinfunction "2_2") (pintype "passive"))
      (node (ref "C13") (pin "2") (pinfunction "2_2") (pintype "passive"))
      (node (ref "C14") (pin "2") (pinfunction "2_2") (pintype "passive"))
      (node (ref "C15") (pin "2") (pinfunction "2_2") (pintype "passive"))
      (node (ref "C16") (pin "1") (pinfunction "1_1") (pintype "passive"))
      (node (ref "C17") (pin "1") (pinfunction "1_1") (pintype "passive"))
      (node (ref "C19") (pin "1") (pinfunction "1_1") (pintype "passive"))
      (node (ref "C22") (pin "1") (pinfunction "1_1") (pintype "passive"))
      (node (ref "C26") (pin "1") (pinfunction "1_1") (pintype "passive"))
      (node (ref "C27") (pin "1") (pinfunction "1_1") (pintype "passive"))
      (node (ref "C28") (pin "1") (pinfunction "1_1") (pintype "passive"))
      (node (ref "C31") (pin "1") (pinfunction "1_1") (pintype "passive"))
      (node (ref "C33") (pin "1") (pinfunction "1_1") (pintype "passive"))
      (node (ref "C34") (pin "1") (pinfunction "1_1") (pintype "passive"))
      (node (ref "C48") (pin "1") (pinfunction "1_1") (pintype "passive"))
      (node (ref "C49") (pin "1") (pinfunction "1_1") (pintype "passive"))
      (node (ref "C50") (pin "1") (pinfunction "1_1") (pintype "passive"))
      (node (ref "IC1") (pin "11") (pinfunction "GND_11") (pintype "power_in"))
      (node (ref "IC1") (pin "12") (pinfunction "GND_12") (pintype "power_in"))
      (node (ref "IC1") (pin "13") (pinfunction "GND_13") (pintype "power_in"))
      (node (ref "IC1") (pin "14") (pinfunction "B8_14") (pintype "bidirectional"))
      (node (ref "IC1") (pin "15") (pinfunction "B7_15") (pintype "bidirectional"))
      (node (ref "IC1") (pin "16") (pinfunction "B6_16") (pintype "bidirectional"))
      (node (ref "IC1") (pin "17") (pinfunction "B5_17") (pintype "bidirectional"))
      (node (ref "IC1") (pin "2") (pinfunction "DIR_2") (pintype "input"))
      (node (ref "IC1") (pin "22") (pinfunction "~{OE}_22") (pintype "input"))
      (node (ref "IC22") (pin "3") (pinfunction "GND_3") (pintype "power_in"))
      (node (ref "IC22") (pin "6") (pinfunction "LV_6") (pintype "input"))
      (node (ref "IC5") (pin "11") (pinfunction "GND_11") (pintype "power_in"))
      (node (ref "IC5") (pin "12") (pinfunction "GND_12") (pintype "power_in"))
      (node (ref "IC5") (pin "13") (pinfunction "GND_13") (pintype "power_in"))
      (node (ref "IC5") (pin "22") (pinfunction "~{OE}_22") (pintype "input"))
      (node (ref "IC5") (pin "3") (pinfunction "A1_3") (pintype "bidirectional"))
      (node (ref "IC5") (pin "4") (pinfunction "A2_4") (pintype "bidirectional"))
      (node (ref "IC6") (pin "4") (pinfunction "V-_4") (pintype "power_in"))
      (node (ref "IC9") (pin "3") (pinfunction "GND_3") (pintype "power_in"))
      (node (ref "IC9") (pin "6") (pinfunction "LV_6") (pintype "input"))
      (node (ref "LD5") (pin "1") (pinfunction "C_1") (pintype "passive"))
      (node (ref "LD6") (pin "1") (pinfunction "C_1") (pintype "passive"))
      (node (ref "LD7") (pin "1") (pinfunction "C_1") (pintype "passive"))
      (node (ref "P1") (pin "2") (pinfunction "2_2") (pintype "passive"))
      (node (ref "P2") (pin "2") (pinfunction "2_2") (pintype "passive"))
      (node (ref "R18") (pin "1") (pinfunction "1_1") (pintype "passive"))
      (node (ref "R23") (pin "1") (pinfunction "1_1") (pintype "passive"))
      (node (ref "R24") (pin "1") (pinfunction "1_1") (pintype "passive"))
      (node (ref "R26") (pin "1") (pinfunction "1_1") (pintype "passive"))
      (node (ref "R29") (pin "1") (pinfunction "1_1") (pintype "passive"))
      (node (ref "R3") (pin "1") (pinfunction "1_1") (pintype "passive"))
      (node (ref "R47") (pin "2") (pinfunction "2_2") (pintype "passive"))
      (node (ref "R48") (pin "2") (pinfunction "2_2") (pintype "passive"))
    )
    (net (code "94") (name "N10V0") (class "Default")
      (node (ref "C49") (pin "2") (pinfunction "2_2") (pintype "passive"))
      (node (ref "L4") (pin "2") (pinfunction "2_2") (pintype "passive"))
      (node (ref "P1") (pin "3") (pinfunction "3_3") (pintype "passive"))
      (node (ref "P2") (pin "3") (pinfunction "3_3") (pintype "passive"))
    )
    (net (code "95") (name "Net-(F1-Pad1)") (class "Default")
      (node (ref "F1") (pin "1") (pinfunction "1_1") (pintype "passive"))
      (node (ref "P1") (pin "1") (pinfunction "1_1") (pintype "passive"))
      (node (ref "R35") (pin "2") (pinfunction "2_2") (pintype "passive"))
    )
    (net (code "96") (name "Net-(F2-Pad1)") (class "Default")
      (node (ref "F2") (pin "1") (pinfunction "1_1") (pintype "passive"))
      (node (ref "P2") (pin "1") (pinfunction "1_1") (pintype "passive"))
      (node (ref "R27") (pin "2") (pinfunction "2_2") (pintype "passive"))
    )
    (net (code "97") (name "Net-(IC6A-IN+)") (class "Default")
      (node (ref "C31") (pin "2") (pinfunction "2_2") (pintype "passive"))
      (node (ref "IC6") (pin "3") (pinfunction "IN+_3") (pintype "input"))
      (node (ref "IC6") (pin "5") (pinfunction "IN+_5") (pintype "input"))
      (node (ref "R21") (pin "1") (pinfunction "1_1") (pintype "passive"))
      (node (ref "R24") (pin "2") (pinfunction "2_2") (pintype "passive"))
    )
    (net (code "98") (name "Net-(IC7-ADJ)") (class "Default")
      (node (ref "IC7") (pin "1") (pinfunction "ADJ_1") (pintype "power_in"))
      (node (ref "R16") (pin "2") (pinfunction "2_2") (pintype "passive"))
      (node (ref "R17") (pin "2") (pinfunction "2_2") (pintype "passive"))
      (node (ref "R18") (pin "2") (pinfunction "2_2") (pintype "passive"))
      (node (ref "R19") (pin "2") (pinfunction "2_2") (pintype "passive"))
    )
    (net (code "99") (name "Net-(IC8-ADJ)") (class "Default")
      (node (ref "IC8") (pin "1") (pinfunction "ADJ_1") (pintype "power_in"))
      (node (ref "R20") (pin "1") (pinfunction "1_1") (pintype "passive"))
      (node (ref "R3") (pin "2") (pinfunction "2_2") (pintype "passive"))
    )
    (net (code "100") (name "Net-(IC9-Cap+)") (class "Default")
      (node (ref "C32") (pin "1") (pinfunction "1_1") (pintype "passive"))
      (node (ref "IC9") (pin "2") (pinfunction "Cap+_2") (pintype "passive"))
    )
    (net (code "101") (name "Net-(IC9-Cap-)") (class "Default")
      (node (ref "C32") (pin "2") (pinfunction "2_2") (pintype "passive"))
      (node (ref "IC9") (pin "4") (pinfunction "Cap-_4") (pintype "passive"))
    )
    (net (code "102") (name "Net-(IC22-Cap+)") (class "Default")
      (node (ref "C47") (pin "1") (pinfunction "1_1") (pintype "passive"))
      (node (ref "IC22") (pin "2") (pinfunction "Cap+_2") (pintype "passive"))
    )
    (net (code "103") (name "Net-(IC22-Cap-)") (class "Default")
      (node (ref "C47") (pin "2") (pinfunction "2_2") (pintype "passive"))
      (node (ref "IC22") (pin "4") (pinfunction "Cap-_4") (pintype "passive"))
    )
    (net (code "104") (name "Net-(IC22-Vout)") (class "Default")
      (node (ref "C33") (pin "2") (pinfunction "2_2") (pintype "passive"))
      (node (ref "C48") (pin "2") (pinfunction "2_2") (pintype "passive"))
      (node (ref "IC22") (pin "5") (pinfunction "Vout_5") (pintype "power_in"))
      (node (ref "IC9") (pin "5") (pinfunction "Vout_5") (pintype "power_in"))
      (node (ref "L4") (pin "1") (pinfunction "1_1") (pintype "passive"))
    )
    (net (code "105") (name "Net-(R30-Pad1)") (class "Default")
      (node (ref "R30") (pin "1") (pinfunction "1_1") (pintype "passive"))
      (node (ref "R31") (pin "2") (pinfunction "2_2") (pintype "passive"))
    )
    (net (code "106") (name "Net-(R32-Pad1)") (class "Default")
      (node (ref "R32") (pin "1") (pinfunction "1_1") (pintype "passive"))
      (node (ref "R33") (pin "2") (pinfunction "2_2") (pintype "passive"))
    )
    (net (code "107") (name "Net-(T1-B)") (class "Default")
      (node (ref "R27") (pin "1") (pinfunction "1_1") (pintype "passive"))
      (node (ref "T1") (pin "1") (pinfunction "B_1") (pintype "passive"))
    )
    (net (code "108") (name "Net-(T1-C)") (class "Default")
      (node (ref "R28") (pin "2") (pinfunction "2_2") (pintype "passive"))
      (node (ref "R32") (pin "2") (pinfunction "2_2") (pintype "passive"))
      (node (ref "T1") (pin "3") (pinfunction "C_3") (pintype "passive"))
    )
    (net (code "109") (name "Net-(T5-B)") (class "Default")
      (node (ref "R35") (pin "1") (pinfunction "1_1") (pintype "passive"))
      (node (ref "T5") (pin "1") (pinfunction "B_1") (pintype "passive"))
    )
    (net (code "110") (name "Net-(T5-C)") (class "Default")
      (node (ref "R25") (pin "2") (pinfunction "2_2") (pintype "passive"))
      (node (ref "R30") (pin "2") (pinfunction "2_2") (pintype "passive"))
      (node (ref "T5") (pin "3") (pinfunction "C_3") (pintype "passive"))
    )
    (net (code "111") (name "P3V3MP") (class "Default")
      (node (ref "C16") (pin "2") (pinfunction "2_2") (pintype "passive"))
      (node (ref "C17") (pin "2") (pinfunction "2_2") (pintype "passive"))
      (node (ref "C22") (pin "2") (pinfunction "2_2") (pintype "passive"))
      (node (ref "C26") (pin "2") (pinfunction "2_2") (pintype "passive"))
      (node (ref "IC1") (pin "1") (pinfunction "VCCA_1") (pintype "power_in"))
      (node (ref "IC1") (pin "23") (pinfunction "VCCB_23") (pintype "power_in"))
      (node (ref "IC5") (pin "1") (pinfunction "VCCA_1") (pintype "power_in"))
      (node (ref "IC5") (pin "2") (pinfunction "DIR_2") (pintype "input"))
      (node (ref "IC5") (pin "23") (pinfunction "VCCB_23") (pintype "power_in"))
    )
    (net (code "112") (name "P5V0") (class "Default")
      (node (ref "C13") (pin "1") (pinfunction "1_1") (pintype "passive"))
      (node (ref "IC7") (pin "2") (pinfunction "OUT_2") (pintype "power_in"))
      (node (ref "IC7") (pin "4") (pinfunction "OUT_4") (pintype "power_in"))
      (node (ref "L2") (pin "1") (pinfunction "1_1") (pintype "passive"))
      (node (ref "R16") (pin "1") (pinfunction "1_1") (pintype "passive"))
      (node (ref "R17") (pin "1") (pinfunction "1_1") (pintype "passive"))
      (node (ref "R19") (pin "1") (pinfunction "1_1") (pintype "passive"))
    )
    (net (code "113") (name "P5V0A") (class "Default")
      (node (ref "C14") (pin "1") (pinfunction "1_1") (pintype "passive"))
      (node (ref "C19") (pin "2") (pinfunction "2_2") (pintype "passive"))
      (node (ref "C27") (pin "2") (pinfunction "2_2") (pintype "passive"))
      (node (ref "C28") (pin "2") (pinfunction "2_2") (pintype "passive"))
      (node (ref "IC1") (pin "24") (pinfunction "VCCB_24") (pintype "power_in"))
      (node (ref "IC5") (pin "24") (pinfunction "VCCB_24") (pintype "power_in"))
      (node (ref "IC6") (pin "8") (pinfunction "V+_8") (pintype "power_in"))
      (node (ref "L2") (pin "2") (pinfunction "2_2") (pintype "passive"))
      (node (ref "R21") (pin "2") (pinfunction "2_2") (pintype "passive"))
      (node (ref "R22") (pin "2") (pinfunction "2_2") (pintype "passive"))
    )
    (net (code "114") (name "P10V0") (class "Default")
      (node (ref "C15") (pin "1") (pinfunction "1_1") (pintype "passive"))
      (node (ref "C34") (pin "2") (pinfunction "2_2") (pintype "passive"))
      (node (ref "C50") (pin "2") (pinfunction "2_2") (pintype "passive"))
      (node (ref "IC22") (pin "8") (pinfunction "V+_8") (pintype "power_in"))
      (node (ref "IC8") (pin "2") (pinfunction "OUT_2") (pintype "power_in"))
      (node (ref "IC8") (pin "4") (pinfunction "OUT_4") (pintype "power_in"))
      (node (ref "IC9") (pin "8") (pinfunction "V+_8") (pintype "power_in"))
      (node (ref "R20") (pin "2") (pinfunction "2_2") (pintype "passive"))
    )
    (net (code "115") (name "P12V0") (class "Default")
      (node (ref "L1") (pin "1") (pinfunction "1_1") (pintype "passive"))
    )
    (net (code "116") (name "P12V0A") (class "Default")
      (node (ref "C12") (pin "1") (pinfunction "1_1") (pintype "passive"))
      (node (ref "F1") (pin "2") (pinfunction "2_2") (pintype "passive"))
      (node (ref "F2") (pin "2") (pinfunction "2_2") (pintype "passive"))
      (node (ref "IC7") (pin "3") (pinfunction "IN_3") (pintype "input"))
      (node (ref "IC8") (pin "3") (pinfunction "IN_3") (pintype "input"))
      (node (ref "L1") (pin "2") (pinfunction "2_2") (pintype "passive"))
      (node (ref "T1") (pin "2") (pinfunction "E_2") (pintype "passive"))
      (node (ref "T5") (pin "2") (pinfunction "E_2") (pintype "passive"))
    )
    (net (code "117") (name "unconnected-(B3-Pad1)") (class "Default")
      (node (ref "B3") (pin "1") (pinfunction "1_1") (pintype "bidirectional"))
    )
    (net (code "118") (name "unconnected-(B4-Pad1)") (class "Default")
      (node (ref "B4") (pin "1") (pinfunction "1_1") (pintype "bidirectional"))
    )
    (net (code "119") (name "unconnected-(B5-Pad1)") (class "Default")
      (node (ref "B5") (pin "1") (pinfunction "1_1") (pintype "bidirectional"))
    )
    (net (code "120") (name "unconnected-(B6-Pad1)") (class "Default")
      (node (ref "B6") (pin "1") (pinfunction "1_1") (pintype "bidirectional"))
    )
    (net (code "121") (name "unconnected-(B7-Pad1)") (class "Default")
      (node (ref "B7") (pin "1") (pinfunction "1_1") (pintype "bidirectional"))
    )
    (net (code "122") (name "unconnected-(B8-Pad1)") (class "Default")
      (node (ref "B8") (pin "1") (pinfunction "1_1") (pintype "bidirectional"))
    )
    (net (code "123") (name "unconnected-(IC1-A5-Pad7)") (class "Default")
      (node (ref "IC1") (pin "7") (pinfunction "A5_7") (pintype "bidirectional"))
    )
    (net (code "124") (name "unconnected-(IC1-A6-Pad8)") (class "Default")
      (node (ref "IC1") (pin "8") (pinfunction "A6_8") (pintype "bidirectional"))
    )
    (net (code "125") (name "unconnected-(IC1-A7-Pad9)") (class "Default")
      (node (ref "IC1") (pin "9") (pinfunction "A7_9") (pintype "bidirectional"))
    )
    (net (code "126") (name "unconnected-(IC1-A8-Pad10)") (class "Default")
      (node (ref "IC1") (pin "10") (pinfunction "A8_10") (pintype "bidirectional"))
    )
    (net (code "127") (name "unconnected-(IC5-B1-Pad21)") (class "Default")
      (node (ref "IC5") (pin "21") (pinfunction "B1_21") (pintype "bidirectional"))
    )
    (net (code "128") (name "unconnected-(IC5-B2-Pad20)") (class "Default")
      (node (ref "IC5") (pin "20") (pinfunction "B2_20") (pintype "bidirectional"))
    )
    (net (code "129") (name "unconnected-(IC9-Boost-Pad1)") (class "Default")
      (node (ref "IC9") (pin "1") (pinfunction "Boost_1") (pintype "passive+no_connect"))
    )
    (net (code "130") (name "unconnected-(IC9-OSC-Pad7)") (class "Default")
      (node (ref "IC9") (pin "7") (pinfunction "OSC_7") (pintype "input+no_connect"))
    )
    (net (code "131") (name "unconnected-(IC22-Boost-Pad1)") (class "Default")
      (node (ref "IC22") (pin "1") (pinfunction "Boost_1") (pintype "passive+no_connect"))
    )
    (net (code "132") (name "unconnected-(IC22-OSC-Pad7)") (class "Default")
      (node (ref "IC22") (pin "7") (pinfunction "OSC_7") (pintype "input+no_connect"))
    )
  )
)
